# RPi2LSD.net
KiCad netlist of a schematic drawn in EAGLE
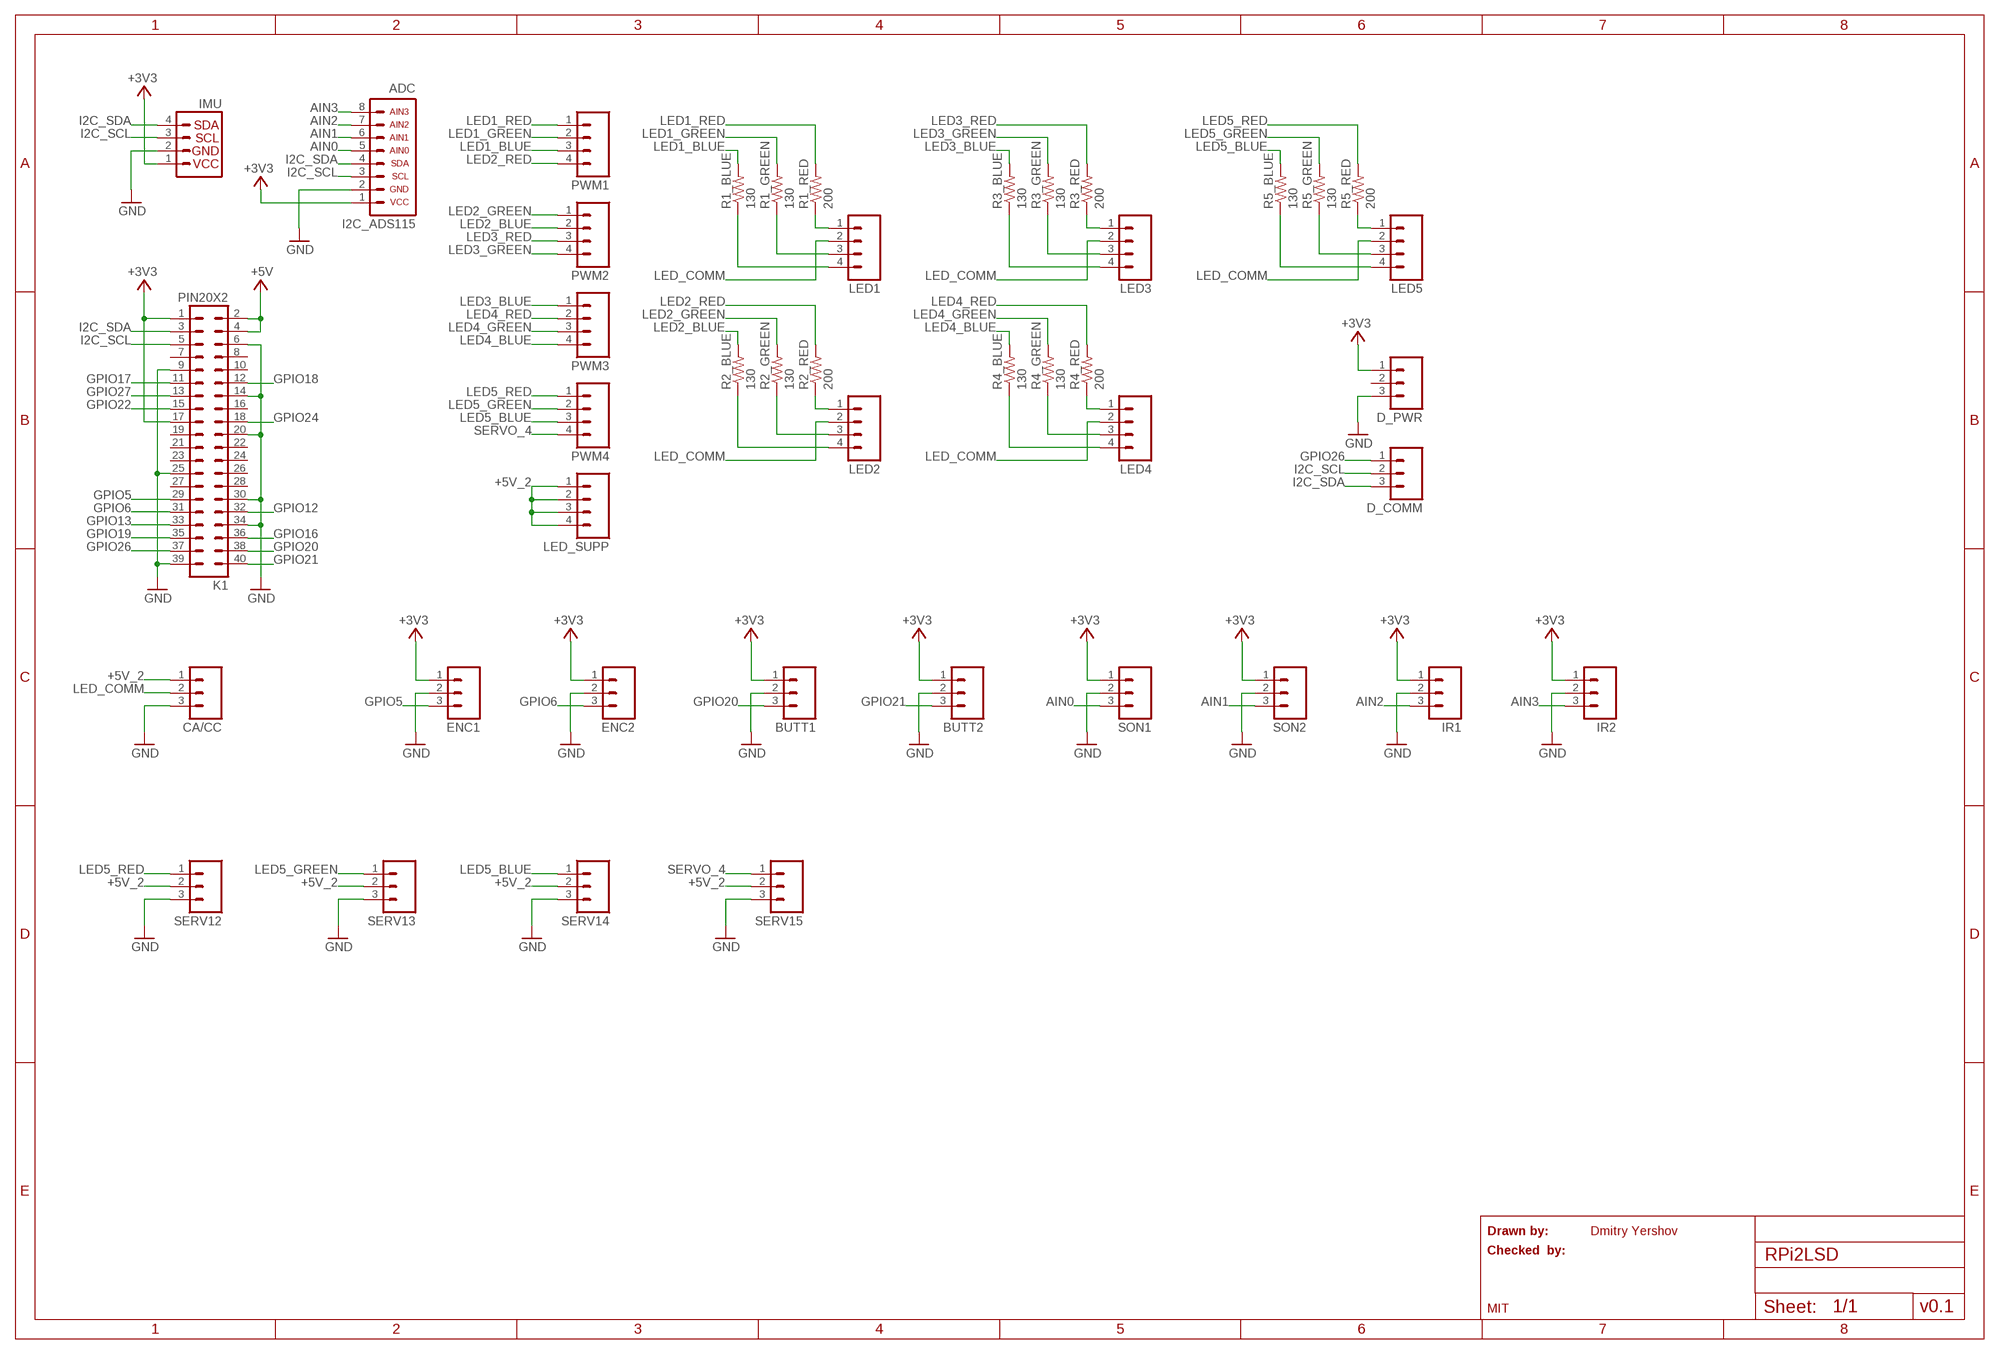
[diagram p0: schematic, sheet 1]

(export (version "E")
  (design (tool "Eeschema 10.0.6"))
  (components
    (comp (ref "ADC")
      (value "I2C_ADS115")
      (footprint "eagle-import:I2C_AX4")
      (libsource (lib "eagle-import") (part "I2C_ADS115"))
    )
    (comp (ref "BUTT1")
      (value "M03PTH")
      (footprint "eagle-import:1X03")
      (libsource (lib "eagle-import") (part "M03PTH"))
    )
    (comp (ref "BUTT2")
      (value "M03PTH")
      (footprint "eagle-import:1X03")
      (libsource (lib "eagle-import") (part "M03PTH"))
    )
    (comp (ref "CA/CC")
      (value "M03PTH")
      (footprint "eagle-import:1X03")
      (libsource (lib "eagle-import") (part "M03PTH"))
    )
    (comp (ref "D_COMM")
      (value "M03PTH")
      (footprint "eagle-import:1X03")
      (libsource (lib "eagle-import") (part "M03PTH"))
    )
    (comp (ref "D_PWR")
      (value "M03PTH")
      (footprint "eagle-import:1X03")
      (libsource (lib "eagle-import") (part "M03PTH"))
    )
    (comp (ref "ENC1")
      (value "M03PTH")
      (footprint "eagle-import:1X03")
      (libsource (lib "eagle-import") (part "M03PTH"))
    )
    (comp (ref "ENC2")
      (value "M03PTH")
      (footprint "eagle-import:1X03")
      (libsource (lib "eagle-import") (part "M03PTH"))
    )
    (comp (ref "IMU")
      (value "I2C_IMU_L3GD20H+LSM303")
      (footprint "eagle-import:1X04")
      (libsource (lib "eagle-import") (part "I2C_IMU_L3GD20H+LSM303"))
    )
    (comp (ref "IR1")
      (value "M03PTH")
      (footprint "eagle-import:1X03")
      (libsource (lib "eagle-import") (part "M03PTH"))
    )
    (comp (ref "IR2")
      (value "M03PTH")
      (footprint "eagle-import:1X03")
      (libsource (lib "eagle-import") (part "M03PTH"))
    )
    (comp (ref "K1")
      (value "PIN20X2")
      (footprint "eagle-import:PIN_20X2")
      (libsource (lib "eagle-import") (part "PIN20X2"))
    )
    (comp (ref "LED1")
      (value "M04PTH")
      (footprint "eagle-import:1X04")
      (libsource (lib "eagle-import") (part "M04PTH"))
    )
    (comp (ref "LED2")
      (value "M04PTH")
      (footprint "eagle-import:1X04")
      (libsource (lib "eagle-import") (part "M04PTH"))
    )
    (comp (ref "LED3")
      (value "M04PTH")
      (footprint "eagle-import:1X04")
      (libsource (lib "eagle-import") (part "M04PTH"))
    )
    (comp (ref "LED4")
      (value "M04PTH")
      (footprint "eagle-import:1X04")
      (libsource (lib "eagle-import") (part "M04PTH"))
    )
    (comp (ref "LED5")
      (value "M04PTH")
      (footprint "eagle-import:1X04")
      (libsource (lib "eagle-import") (part "M04PTH"))
    )
    (comp (ref "LED_SUPP")
      (value "M041X04_NO_SILK")
      (footprint "eagle-import:1X04_NO_SILK")
      (libsource (lib "eagle-import") (part "M041X04_NO_SILK"))
    )
    (comp (ref "PWM1")
      (value "M041X04_NO_SILK")
      (footprint "eagle-import:1X04_NO_SILK")
      (libsource (lib "eagle-import") (part "M041X04_NO_SILK"))
    )
    (comp (ref "PWM2")
      (value "M041X04_NO_SILK")
      (footprint "eagle-import:1X04_NO_SILK")
      (libsource (lib "eagle-import") (part "M041X04_NO_SILK"))
    )
    (comp (ref "PWM3")
      (value "M041X04_NO_SILK")
      (footprint "eagle-import:1X04_NO_SILK")
      (libsource (lib "eagle-import") (part "M041X04_NO_SILK"))
    )
    (comp (ref "PWM4")
      (value "M041X04_NO_SILK")
      (footprint "eagle-import:1X04_NO_SILK")
      (libsource (lib "eagle-import") (part "M041X04_NO_SILK"))
    )
    (comp (ref "R1_BLUE")
      (value "130")
      (footprint "eagle-import:0207_9")
      (libsource (lib "eagle-import") (part "R-US_0207/9"))
    )
    (comp (ref "R1_GREEN")
      (value "130")
      (footprint "eagle-import:0207_9")
      (libsource (lib "eagle-import") (part "R-US_0207/9"))
    )
    (comp (ref "R1_RED")
      (value "200")
      (footprint "eagle-import:0207_9")
      (libsource (lib "eagle-import") (part "R-US_0207/9"))
    )
    (comp (ref "R2_BLUE")
      (value "130")
      (footprint "eagle-import:0207_9")
      (libsource (lib "eagle-import") (part "R-US_0207/9"))
    )
    (comp (ref "R2_GREEN")
      (value "130")
      (footprint "eagle-import:0207_9")
      (libsource (lib "eagle-import") (part "R-US_0207/9"))
    )
    (comp (ref "R2_RED")
      (value "200")
      (footprint "eagle-import:0207_9")
      (libsource (lib "eagle-import") (part "R-US_0207/9"))
    )
    (comp (ref "R3_BLUE")
      (value "130")
      (footprint "eagle-import:0207_9")
      (libsource (lib "eagle-import") (part "R-US_0207/9"))
    )
    (comp (ref "R3_GREEN")
      (value "130")
      (footprint "eagle-import:0207_9")
      (libsource (lib "eagle-import") (part "R-US_0207/9"))
    )
    (comp (ref "R3_RED")
      (value "200")
      (footprint "eagle-import:0207_9")
      (libsource (lib "eagle-import") (part "R-US_0207/9"))
    )
    (comp (ref "R4_BLUE")
      (value "130")
      (footprint "eagle-import:0207_9")
      (libsource (lib "eagle-import") (part "R-US_0207/9"))
    )
    (comp (ref "R4_GREEN")
      (value "130")
      (footprint "eagle-import:0207_9")
      (libsource (lib "eagle-import") (part "R-US_0207/9"))
    )
    (comp (ref "R4_RED")
      (value "200")
      (footprint "eagle-import:0207_9")
      (libsource (lib "eagle-import") (part "R-US_0207/9"))
    )
    (comp (ref "R5_BLUE")
      (value "130")
      (footprint "eagle-import:0207_9")
      (libsource (lib "eagle-import") (part "R-US_0207/9"))
    )
    (comp (ref "R5_GREEN")
      (value "130")
      (footprint "eagle-import:0207_9")
      (libsource (lib "eagle-import") (part "R-US_0207/9"))
    )
    (comp (ref "R5_RED")
      (value "200")
      (footprint "eagle-import:0207_9")
      (libsource (lib "eagle-import") (part "R-US_0207/9"))
    )
    (comp (ref "SERV12")
      (value "M03PTH")
      (footprint "eagle-import:1X03")
      (libsource (lib "eagle-import") (part "M03PTH"))
    )
    (comp (ref "SERV13")
      (value "M03PTH")
      (footprint "eagle-import:1X03")
      (libsource (lib "eagle-import") (part "M03PTH"))
    )
    (comp (ref "SERV14")
      (value "M03PTH")
      (footprint "eagle-import:1X03")
      (libsource (lib "eagle-import") (part "M03PTH"))
    )
    (comp (ref "SERV15")
      (value "M03PTH")
      (footprint "eagle-import:1X03")
      (libsource (lib "eagle-import") (part "M03PTH"))
    )
    (comp (ref "SON1")
      (value "M03PTH")
      (footprint "eagle-import:1X03")
      (libsource (lib "eagle-import") (part "M03PTH"))
    )
    (comp (ref "SON2")
      (value "M03PTH")
      (footprint "eagle-import:1X03")
      (libsource (lib "eagle-import") (part "M03PTH"))
    )
  )
  (nets
    (net (code "1") (name "+3V3") (class "Default")
      (node (ref "ADC") (pin "1") (pinfunction "1_1") (pintype "passive"))
      (node (ref "BUTT1") (pin "1") (pinfunction "1_1") (pintype "passive"))
      (node (ref "BUTT2") (pin "1") (pinfunction "1_1") (pintype "passive"))
      (node (ref "D_PWR") (pin "1") (pinfunction "1_1") (pintype "passive"))
      (node (ref "ENC1") (pin "1") (pinfunction "1_1") (pintype "passive"))
      (node (ref "ENC2") (pin "1") (pinfunction "1_1") (pintype "passive"))
      (node (ref "IMU") (pin "1") (pinfunction "1_1") (pintype "passive"))
      (node (ref "IR1") (pin "1") (pinfunction "1_1") (pintype "passive"))
      (node (ref "IR2") (pin "1") (pinfunction "1_1") (pintype "passive"))
      (node (ref "K1") (pin "1") (pinfunction "1_1") (pintype "passive"))
      (node (ref "K1") (pin "17") (pinfunction "17_17") (pintype "passive"))
      (node (ref "SON1") (pin "1") (pinfunction "1_1") (pintype "passive"))
      (node (ref "SON2") (pin "1") (pinfunction "1_1") (pintype "passive"))
    )
    (net (code "2") (name "+5V") (class "Default")
      (node (ref "K1") (pin "2") (pinfunction "2_2") (pintype "passive"))
      (node (ref "K1") (pin "4") (pinfunction "4_4") (pintype "passive"))
    )
    (net (code "3") (name "/+5V_2") (class "Default")
      (node (ref "CA/CC") (pin "1") (pinfunction "1_1") (pintype "passive"))
      (node (ref "LED_SUPP") (pin "1") (pinfunction "1_1") (pintype "passive"))
      (node (ref "LED_SUPP") (pin "2") (pinfunction "2_2") (pintype "passive"))
      (node (ref "LED_SUPP") (pin "3") (pinfunction "3_3") (pintype "passive"))
      (node (ref "LED_SUPP") (pin "4") (pinfunction "4_4") (pintype "passive"))
      (node (ref "SERV12") (pin "2") (pinfunction "2_2") (pintype "passive"))
      (node (ref "SERV13") (pin "2") (pinfunction "2_2") (pintype "passive"))
      (node (ref "SERV14") (pin "2") (pinfunction "2_2") (pintype "passive"))
      (node (ref "SERV15") (pin "2") (pinfunction "2_2") (pintype "passive"))
    )
    (net (code "4") (name "/AIN0") (class "Default")
      (node (ref "ADC") (pin "5") (pinfunction "5_5") (pintype "passive"))
      (node (ref "SON1") (pin "3") (pinfunction "3_3") (pintype "passive"))
    )
    (net (code "5") (name "/AIN1") (class "Default")
      (node (ref "ADC") (pin "6") (pinfunction "6_6") (pintype "passive"))
      (node (ref "SON2") (pin "3") (pinfunction "3_3") (pintype "passive"))
    )
    (net (code "6") (name "/AIN2") (class "Default")
      (node (ref "ADC") (pin "7") (pinfunction "7_7") (pintype "passive"))
      (node (ref "IR1") (pin "3") (pinfunction "3_3") (pintype "passive"))
    )
    (net (code "7") (name "/AIN3") (class "Default")
      (node (ref "ADC") (pin "8") (pinfunction "8_8") (pintype "passive"))
      (node (ref "IR2") (pin "3") (pinfunction "3_3") (pintype "passive"))
    )
    (net (code "8") (name "/GPIO5") (class "Default")
      (node (ref "ENC1") (pin "3") (pinfunction "3_3") (pintype "passive"))
      (node (ref "K1") (pin "29") (pinfunction "29_29") (pintype "passive"))
    )
    (net (code "9") (name "/GPIO6") (class "Default")
      (node (ref "ENC2") (pin "3") (pinfunction "3_3") (pintype "passive"))
      (node (ref "K1") (pin "31") (pinfunction "31_31") (pintype "passive"))
    )
    (net (code "10") (name "/GPIO12") (class "Default")
      (node (ref "K1") (pin "32") (pinfunction "32_32") (pintype "passive"))
    )
    (net (code "11") (name "/GPIO13") (class "Default")
      (node (ref "K1") (pin "33") (pinfunction "33_33") (pintype "passive"))
    )
    (net (code "12") (name "/GPIO16") (class "Default")
      (node (ref "K1") (pin "36") (pinfunction "36_36") (pintype "passive"))
    )
    (net (code "13") (name "/GPIO17") (class "Default")
      (node (ref "K1") (pin "11") (pinfunction "11_11") (pintype "passive"))
    )
    (net (code "14") (name "/GPIO18") (class "Default")
      (node (ref "K1") (pin "12") (pinfunction "12_12") (pintype "passive"))
    )
    (net (code "15") (name "/GPIO19") (class "Default")
      (node (ref "K1") (pin "35") (pinfunction "35_35") (pintype "passive"))
    )
    (net (code "16") (name "/GPIO20") (class "Default")
      (node (ref "BUTT1") (pin "3") (pinfunction "3_3") (pintype "passive"))
      (node (ref "K1") (pin "38") (pinfunction "38_38") (pintype "passive"))
    )
    (net (code "17") (name "/GPIO21") (class "Default")
      (node (ref "BUTT2") (pin "3") (pinfunction "3_3") (pintype "passive"))
      (node (ref "K1") (pin "40") (pinfunction "40_40") (pintype "passive"))
    )
    (net (code "18") (name "/GPIO22") (class "Default")
      (node (ref "K1") (pin "15") (pinfunction "15_15") (pintype "passive"))
    )
    (net (code "19") (name "/GPIO24") (class "Default")
      (node (ref "K1") (pin "18") (pinfunction "18_18") (pintype "passive"))
    )
    (net (code "20") (name "/GPIO26") (class "Default")
      (node (ref "D_COMM") (pin "1") (pinfunction "1_1") (pintype "passive"))
      (node (ref "K1") (pin "37") (pinfunction "37_37") (pintype "passive"))
    )
    (net (code "21") (name "/GPIO27") (class "Default")
      (node (ref "K1") (pin "13") (pinfunction "13_13") (pintype "passive"))
    )
    (net (code "22") (name "/I2C_SCL") (class "Default")
      (node (ref "ADC") (pin "3") (pinfunction "3_3") (pintype "passive"))
      (node (ref "D_COMM") (pin "2") (pinfunction "2_2") (pintype "passive"))
      (node (ref "IMU") (pin "3") (pinfunction "3_3") (pintype "passive"))
      (node (ref "K1") (pin "5") (pinfunction "5_5") (pintype "passive"))
    )
    (net (code "23") (name "/I2C_SDA") (class "Default")
      (node (ref "ADC") (pin "4") (pinfunction "4_4") (pintype "passive"))
      (node (ref "D_COMM") (pin "3") (pinfunction "3_3") (pintype "passive"))
      (node (ref "IMU") (pin "4") (pinfunction "4_4") (pintype "passive"))
      (node (ref "K1") (pin "3") (pinfunction "3_3") (pintype "passive"))
    )
    (net (code "24") (name "/LED1_BLUE") (class "Default")
      (node (ref "PWM1") (pin "3") (pinfunction "3_3") (pintype "passive"))
      (node (ref "R1_BLUE") (pin "2") (pinfunction "2_2") (pintype "passive"))
    )
    (net (code "25") (name "/LED1_GREEN") (class "Default")
      (node (ref "PWM1") (pin "2") (pinfunction "2_2") (pintype "passive"))
      (node (ref "R1_GREEN") (pin "2") (pinfunction "2_2") (pintype "passive"))
    )
    (net (code "26") (name "/LED1_RED") (class "Default")
      (node (ref "PWM1") (pin "1") (pinfunction "1_1") (pintype "passive"))
      (node (ref "R1_RED") (pin "2") (pinfunction "2_2") (pintype "passive"))
    )
    (net (code "27") (name "/LED2_BLUE") (class "Default")
      (node (ref "PWM2") (pin "2") (pinfunction "2_2") (pintype "passive"))
      (node (ref "R2_BLUE") (pin "2") (pinfunction "2_2") (pintype "passive"))
    )
    (net (code "28") (name "/LED2_GREEN") (class "Default")
      (node (ref "PWM2") (pin "1") (pinfunction "1_1") (pintype "passive"))
      (node (ref "R2_GREEN") (pin "2") (pinfunction "2_2") (pintype "passive"))
    )
    (net (code "29") (name "/LED2_RED") (class "Default")
      (node (ref "PWM1") (pin "4") (pinfunction "4_4") (pintype "passive"))
      (node (ref "R2_RED") (pin "2") (pinfunction "2_2") (pintype "passive"))
    )
    (net (code "30") (name "/LED3_BLUE") (class "Default")
      (node (ref "PWM3") (pin "1") (pinfunction "1_1") (pintype "passive"))
      (node (ref "R3_BLUE") (pin "2") (pinfunction "2_2") (pintype "passive"))
    )
    (net (code "31") (name "/LED3_GREEN") (class "Default")
      (node (ref "PWM2") (pin "4") (pinfunction "4_4") (pintype "passive"))
      (node (ref "R3_GREEN") (pin "2") (pinfunction "2_2") (pintype "passive"))
    )
    (net (code "32") (name "/LED3_RED") (class "Default")
      (node (ref "PWM2") (pin "3") (pinfunction "3_3") (pintype "passive"))
      (node (ref "R3_RED") (pin "2") (pinfunction "2_2") (pintype "passive"))
    )
    (net (code "33") (name "/LED4_BLUE") (class "Default")
      (node (ref "PWM3") (pin "4") (pinfunction "4_4") (pintype "passive"))
      (node (ref "R4_BLUE") (pin "2") (pinfunction "2_2") (pintype "passive"))
    )
    (net (code "34") (name "/LED4_GREEN") (class "Default")
      (node (ref "PWM3") (pin "3") (pinfunction "3_3") (pintype "passive"))
      (node (ref "R4_GREEN") (pin "2") (pinfunction "2_2") (pintype "passive"))
    )
    (net (code "35") (name "/LED4_RED") (class "Default")
      (node (ref "PWM3") (pin "2") (pinfunction "2_2") (pintype "passive"))
      (node (ref "R4_RED") (pin "2") (pinfunction "2_2") (pintype "passive"))
    )
    (net (code "36") (name "/LED5_BLUE") (class "Default")
      (node (ref "PWM4") (pin "3") (pinfunction "3_3") (pintype "passive"))
      (node (ref "R5_BLUE") (pin "2") (pinfunction "2_2") (pintype "passive"))
      (node (ref "SERV14") (pin "1") (pinfunction "1_1") (pintype "passive"))
    )
    (net (code "37") (name "/LED5_GREEN") (class "Default")
      (node (ref "PWM4") (pin "2") (pinfunction "2_2") (pintype "passive"))
      (node (ref "R5_GREEN") (pin "2") (pinfunction "2_2") (pintype "passive"))
      (node (ref "SERV13") (pin "1") (pinfunction "1_1") (pintype "passive"))
    )
    (net (code "38") (name "/LED5_RED") (class "Default")
      (node (ref "PWM4") (pin "1") (pinfunction "1_1") (pintype "passive"))
      (node (ref "R5_RED") (pin "2") (pinfunction "2_2") (pintype "passive"))
      (node (ref "SERV12") (pin "1") (pinfunction "1_1") (pintype "passive"))
    )
    (net (code "39") (name "/LED_COMM") (class "Default")
      (node (ref "CA/CC") (pin "2") (pinfunction "2_2") (pintype "passive"))
      (node (ref "LED1") (pin "2") (pinfunction "2_2") (pintype "passive"))
      (node (ref "LED2") (pin "2") (pinfunction "2_2") (pintype "passive"))
      (node (ref "LED3") (pin "2") (pinfunction "2_2") (pintype "passive"))
      (node (ref "LED4") (pin "2") (pinfunction "2_2") (pintype "passive"))
      (node (ref "LED5") (pin "2") (pinfunction "2_2") (pintype "passive"))
    )
    (net (code "40") (name "/SERVO_4") (class "Default")
      (node (ref "PWM4") (pin "4") (pinfunction "4_4") (pintype "passive"))
      (node (ref "SERV15") (pin "1") (pinfunction "1_1") (pintype "passive"))
    )
    (net (code "41") (name "GND") (class "Default")
      (node (ref "ADC") (pin "2") (pinfunction "2_2") (pintype "passive"))
      (node (ref "BUTT1") (pin "2") (pinfunction "2_2") (pintype "passive"))
      (node (ref "BUTT2") (pin "2") (pinfunction "2_2") (pintype "passive"))
      (node (ref "CA/CC") (pin "3") (pinfunction "3_3") (pintype "passive"))
      (node (ref "D_PWR") (pin "3") (pinfunction "3_3") (pintype "passive"))
      (node (ref "ENC1") (pin "2") (pinfunction "2_2") (pintype "passive"))
      (node (ref "ENC2") (pin "2") (pinfunction "2_2") (pintype "passive"))
      (node (ref "IMU") (pin "2") (pinfunction "2_2") (pintype "passive"))
      (node (ref "IR1") (pin "2") (pinfunction "2_2") (pintype "passive"))
      (node (ref "IR2") (pin "2") (pinfunction "2_2") (pintype "passive"))
      (node (ref "K1") (pin "14") (pinfunction "14_14") (pintype "passive"))
      (node (ref "K1") (pin "20") (pinfunction "20_20") (pintype "passive"))
      (node (ref "K1") (pin "25") (pinfunction "25_25") (pintype "passive"))
      (node (ref "K1") (pin "30") (pinfunction "30_30") (pintype "passive"))
      (node (ref "K1") (pin "34") (pinfunction "34_34") (pintype "passive"))
      (node (ref "K1") (pin "39") (pinfunction "39_39") (pintype "passive"))
      (node (ref "K1") (pin "6") (pinfunction "6_6") (pintype "passive"))
      (node (ref "K1") (pin "9") (pinfunction "9_9") (pintype "passive"))
      (node (ref "SERV12") (pin "3") (pinfunction "3_3") (pintype "passive"))
      (node (ref "SERV13") (pin "3") (pinfunction "3_3") (pintype "passive"))
      (node (ref "SERV14") (pin "3") (pinfunction "3_3") (pintype "passive"))
      (node (ref "SERV15") (pin "3") (pinfunction "3_3") (pintype "passive"))
      (node (ref "SON1") (pin "2") (pinfunction "2_2") (pintype "passive"))
      (node (ref "SON2") (pin "2") (pinfunction "2_2") (pintype "passive"))
    )
    (net (code "42") (name "Net-(LED1-Pad1)") (class "Default")
      (node (ref "LED1") (pin "1") (pinfunction "1_1") (pintype "passive"))
      (node (ref "R1_RED") (pin "1") (pinfunction "1_1") (pintype "passive"))
    )
    (net (code "43") (name "Net-(LED1-Pad3)") (class "Default")
      (node (ref "LED1") (pin "3") (pinfunction "3_3") (pintype "passive"))
      (node (ref "R1_GREEN") (pin "1") (pinfunction "1_1") (pintype "passive"))
    )
    (net (code "44") (name "Net-(LED1-Pad4)") (class "Default")
      (node (ref "LED1") (pin "4") (pinfunction "4_4") (pintype "passive"))
      (node (ref "R1_BLUE") (pin "1") (pinfunction "1_1") (pintype "passive"))
    )
    (net (code "45") (name "Net-(LED2-Pad1)") (class "Default")
      (node (ref "LED2") (pin "1") (pinfunction "1_1") (pintype "passive"))
      (node (ref "R2_RED") (pin "1") (pinfunction "1_1") (pintype "passive"))
    )
    (net (code "46") (name "Net-(LED2-Pad3)") (class "Default")
      (node (ref "LED2") (pin "3") (pinfunction "3_3") (pintype "passive"))
      (node (ref "R2_GREEN") (pin "1") (pinfunction "1_1") (pintype "passive"))
    )
    (net (code "47") (name "Net-(LED2-Pad4)") (class "Default")
      (node (ref "LED2") (pin "4") (pinfunction "4_4") (pintype "passive"))
      (node (ref "R2_BLUE") (pin "1") (pinfunction "1_1") (pintype "passive"))
    )
    (net (code "48") (name "Net-(LED3-Pad1)") (class "Default")
      (node (ref "LED3") (pin "1") (pinfunction "1_1") (pintype "passive"))
      (node (ref "R3_RED") (pin "1") (pinfunction "1_1") (pintype "passive"))
    )
    (net (code "49") (name "Net-(LED3-Pad3)") (class "Default")
      (node (ref "LED3") (pin "3") (pinfunction "3_3") (pintype "passive"))
      (node (ref "R3_GREEN") (pin "1") (pinfunction "1_1") (pintype "passive"))
    )
    (net (code "50") (name "Net-(LED3-Pad4)") (class "Default")
      (node (ref "LED3") (pin "4") (pinfunction "4_4") (pintype "passive"))
      (node (ref "R3_BLUE") (pin "1") (pinfunction "1_1") (pintype "passive"))
    )
    (net (code "51") (name "Net-(LED4-Pad1)") (class "Default")
      (node (ref "LED4") (pin "1") (pinfunction "1_1") (pintype "passive"))
      (node (ref "R4_RED") (pin "1") (pinfunction "1_1") (pintype "passive"))
    )
    (net (code "52") (name "Net-(LED4-Pad3)") (class "Default")
      (node (ref "LED4") (pin "3") (pinfunction "3_3") (pintype "passive"))
      (node (ref "R4_GREEN") (pin "1") (pinfunction "1_1") (pintype "passive"))
    )
    (net (code "53") (name "Net-(LED4-Pad4)") (class "Default")
      (node (ref "LED4") (pin "4") (pinfunction "4_4") (pintype "passive"))
      (node (ref "R4_BLUE") (pin "1") (pinfunction "1_1") (pintype "passive"))
    )
    (net (code "54") (name "Net-(LED5-Pad1)") (class "Default")
      (node (ref "LED5") (pin "1") (pinfunction "1_1") (pintype "passive"))
      (node (ref "R5_RED") (pin "1") (pinfunction "1_1") (pintype "passive"))
    )
    (net (code "55") (name "Net-(LED5-Pad3)") (class "Default")
      (node (ref "LED5") (pin "3") (pinfunction "3_3") (pintype "passive"))
      (node (ref "R5_GREEN") (pin "1") (pinfunction "1_1") (pintype "passive"))
    )
    (net (code "56") (name "Net-(LED5-Pad4)") (class "Default")
      (node (ref "LED5") (pin "4") (pinfunction "4_4") (pintype "passive"))
      (node (ref "R5_BLUE") (pin "1") (pinfunction "1_1") (pintype "passive"))
    )
    (net (code "57") (name "unconnected-(D_PWR-Pad2)") (class "Default")
      (node (ref "D_PWR") (pin "2") (pinfunction "2_2") (pintype "passive"))
    )
    (net (code "58") (name "unconnected-(K1-Pad7)") (class "Default")
      (node (ref "K1") (pin "7") (pinfunction "7_7") (pintype "passive"))
    )
    (net (code "59") (name "unconnected-(K1-Pad8)") (class "Default")
      (node (ref "K1") (pin "8") (pinfunction "8_8") (pintype "passive"))
    )
    (net (code "60") (name "unconnected-(K1-Pad10)") (class "Default")
      (node (ref "K1") (pin "10") (pinfunction "10_10") (pintype "passive"))
    )
    (net (code "61") (name "unconnected-(K1-Pad16)") (class "Default")
      (node (ref "K1") (pin "16") (pinfunction "16_16") (pintype "passive"))
    )
    (net (code "62") (name "unconnected-(K1-Pad19)") (class "Default")
      (node (ref "K1") (pin "19") (pinfunction "19_19") (pintype "passive"))
    )
    (net (code "63") (name "unconnected-(K1-Pad21)") (class "Default")
      (node (ref "K1") (pin "21") (pinfunction "21_21") (pintype "passive"))
    )
    (net (code "64") (name "unconnected-(K1-Pad22)") (class "Default")
      (node (ref "K1") (pin "22") (pinfunction "22_22") (pintype "passive"))
    )
    (net (code "65") (name "unconnected-(K1-Pad23)") (class "Default")
      (node (ref "K1") (pin "23") (pinfunction "23_23") (pintype "passive"))
    )
    (net (code "66") (name "unconnected-(K1-Pad24)") (class "Default")
      (node (ref "K1") (pin "24") (pinfunction "24_24") (pintype "passive"))
    )
    (net (code "67") (name "unconnected-(K1-Pad26)") (class "Default")
      (node (ref "K1") (pin "26") (pinfunction "26_26") (pintype "passive"))
    )
    (net (code "68") (name "unconnected-(K1-Pad27)") (class "Default")
      (node (ref "K1") (pin "27") (pinfunction "27_27") (pintype "passive"))
    )
    (net (code "69") (name "unconnected-(K1-Pad28)") (class "Default")
      (node (ref "K1") (pin "28") (pinfunction "28_28") (pintype "passive"))
    )
  )
)
